# Jump_Stater.net
KiCad netlist of a schematic drawn in Altium Designer
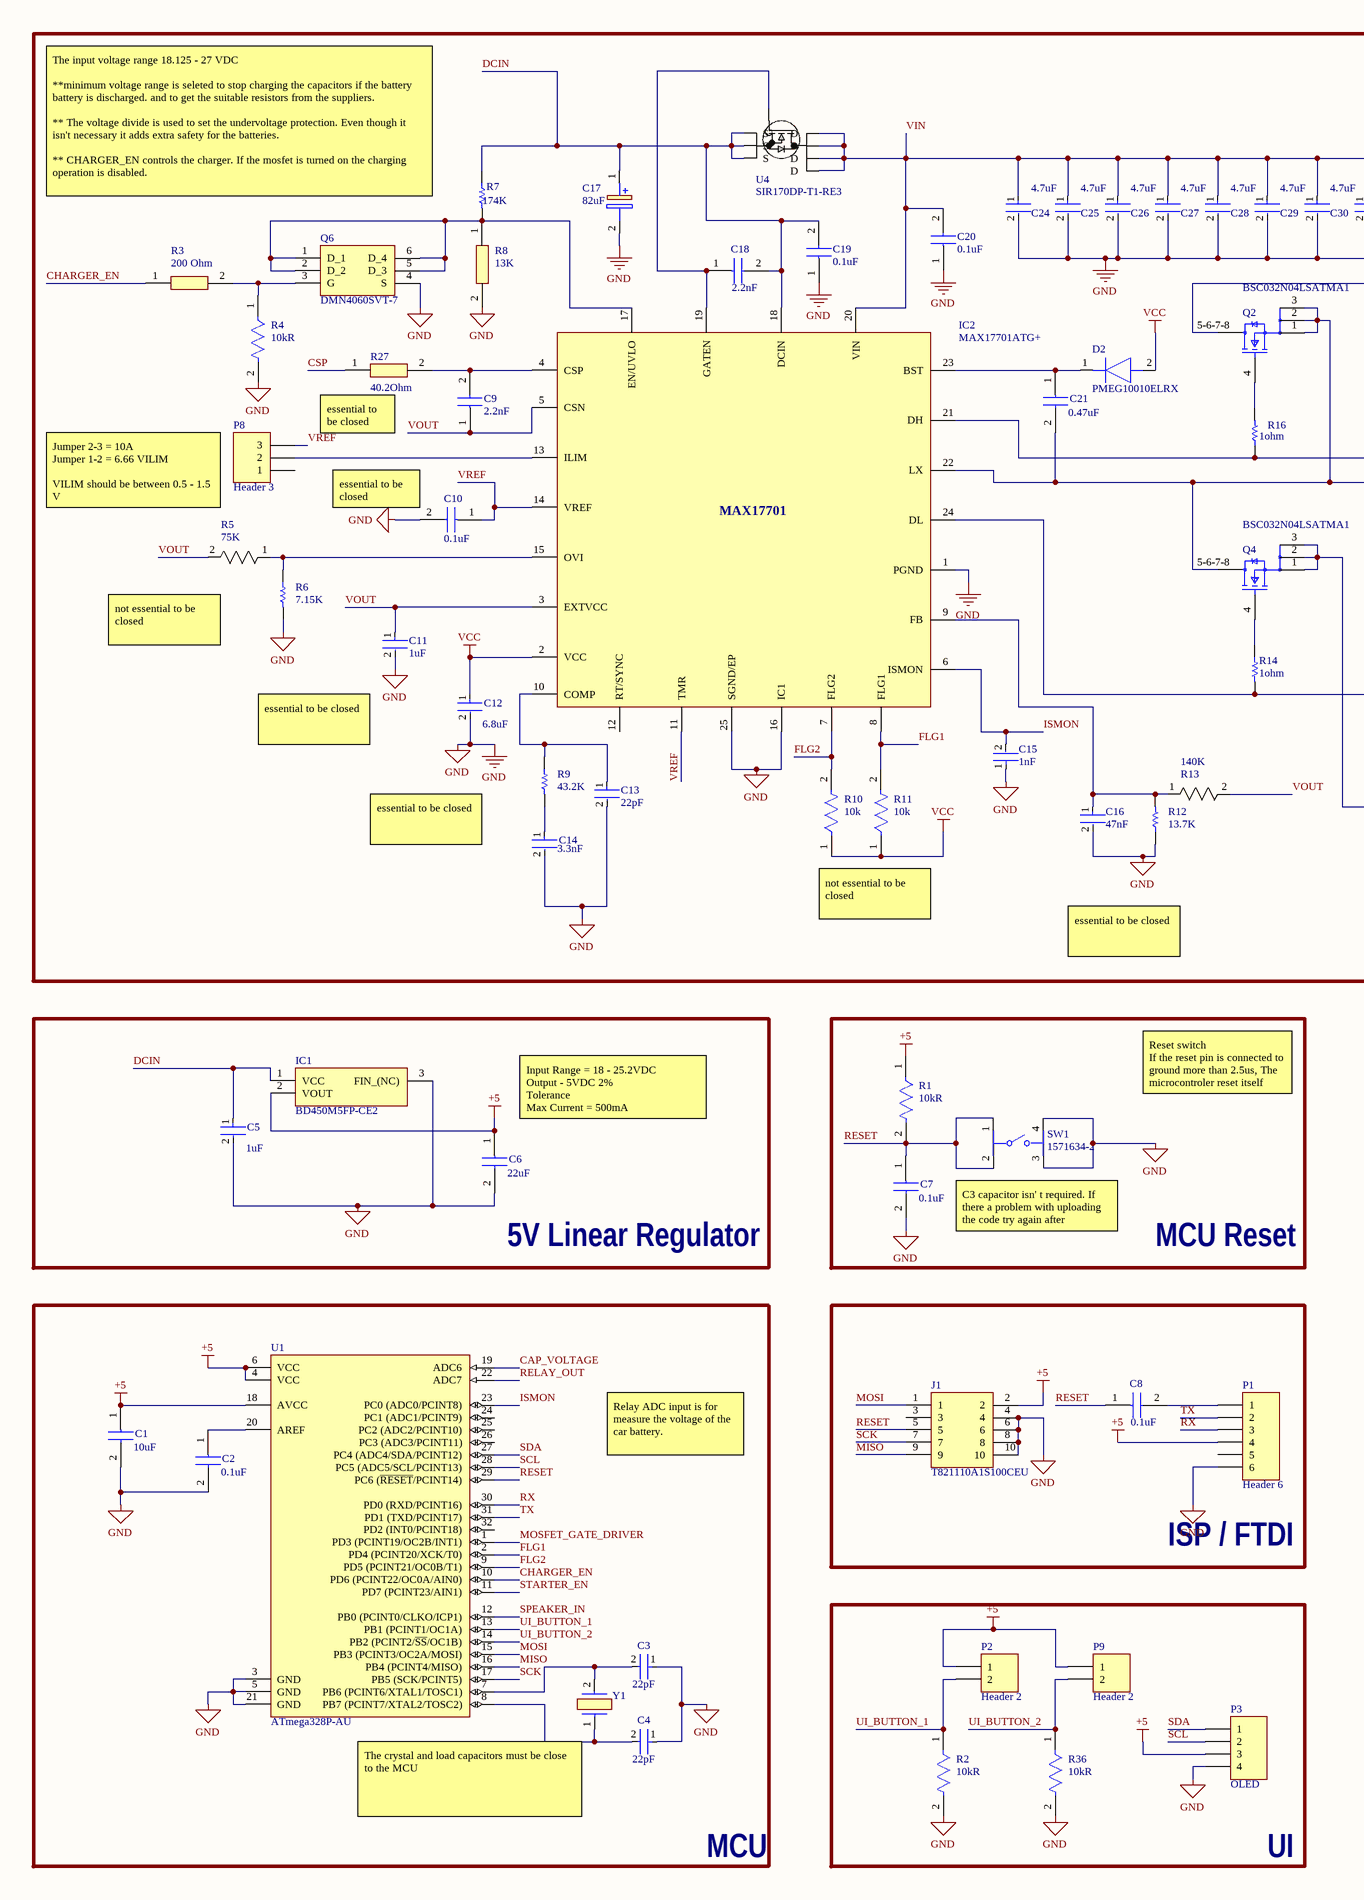
[diagram p0: Jump Stater.SchDoc, left]
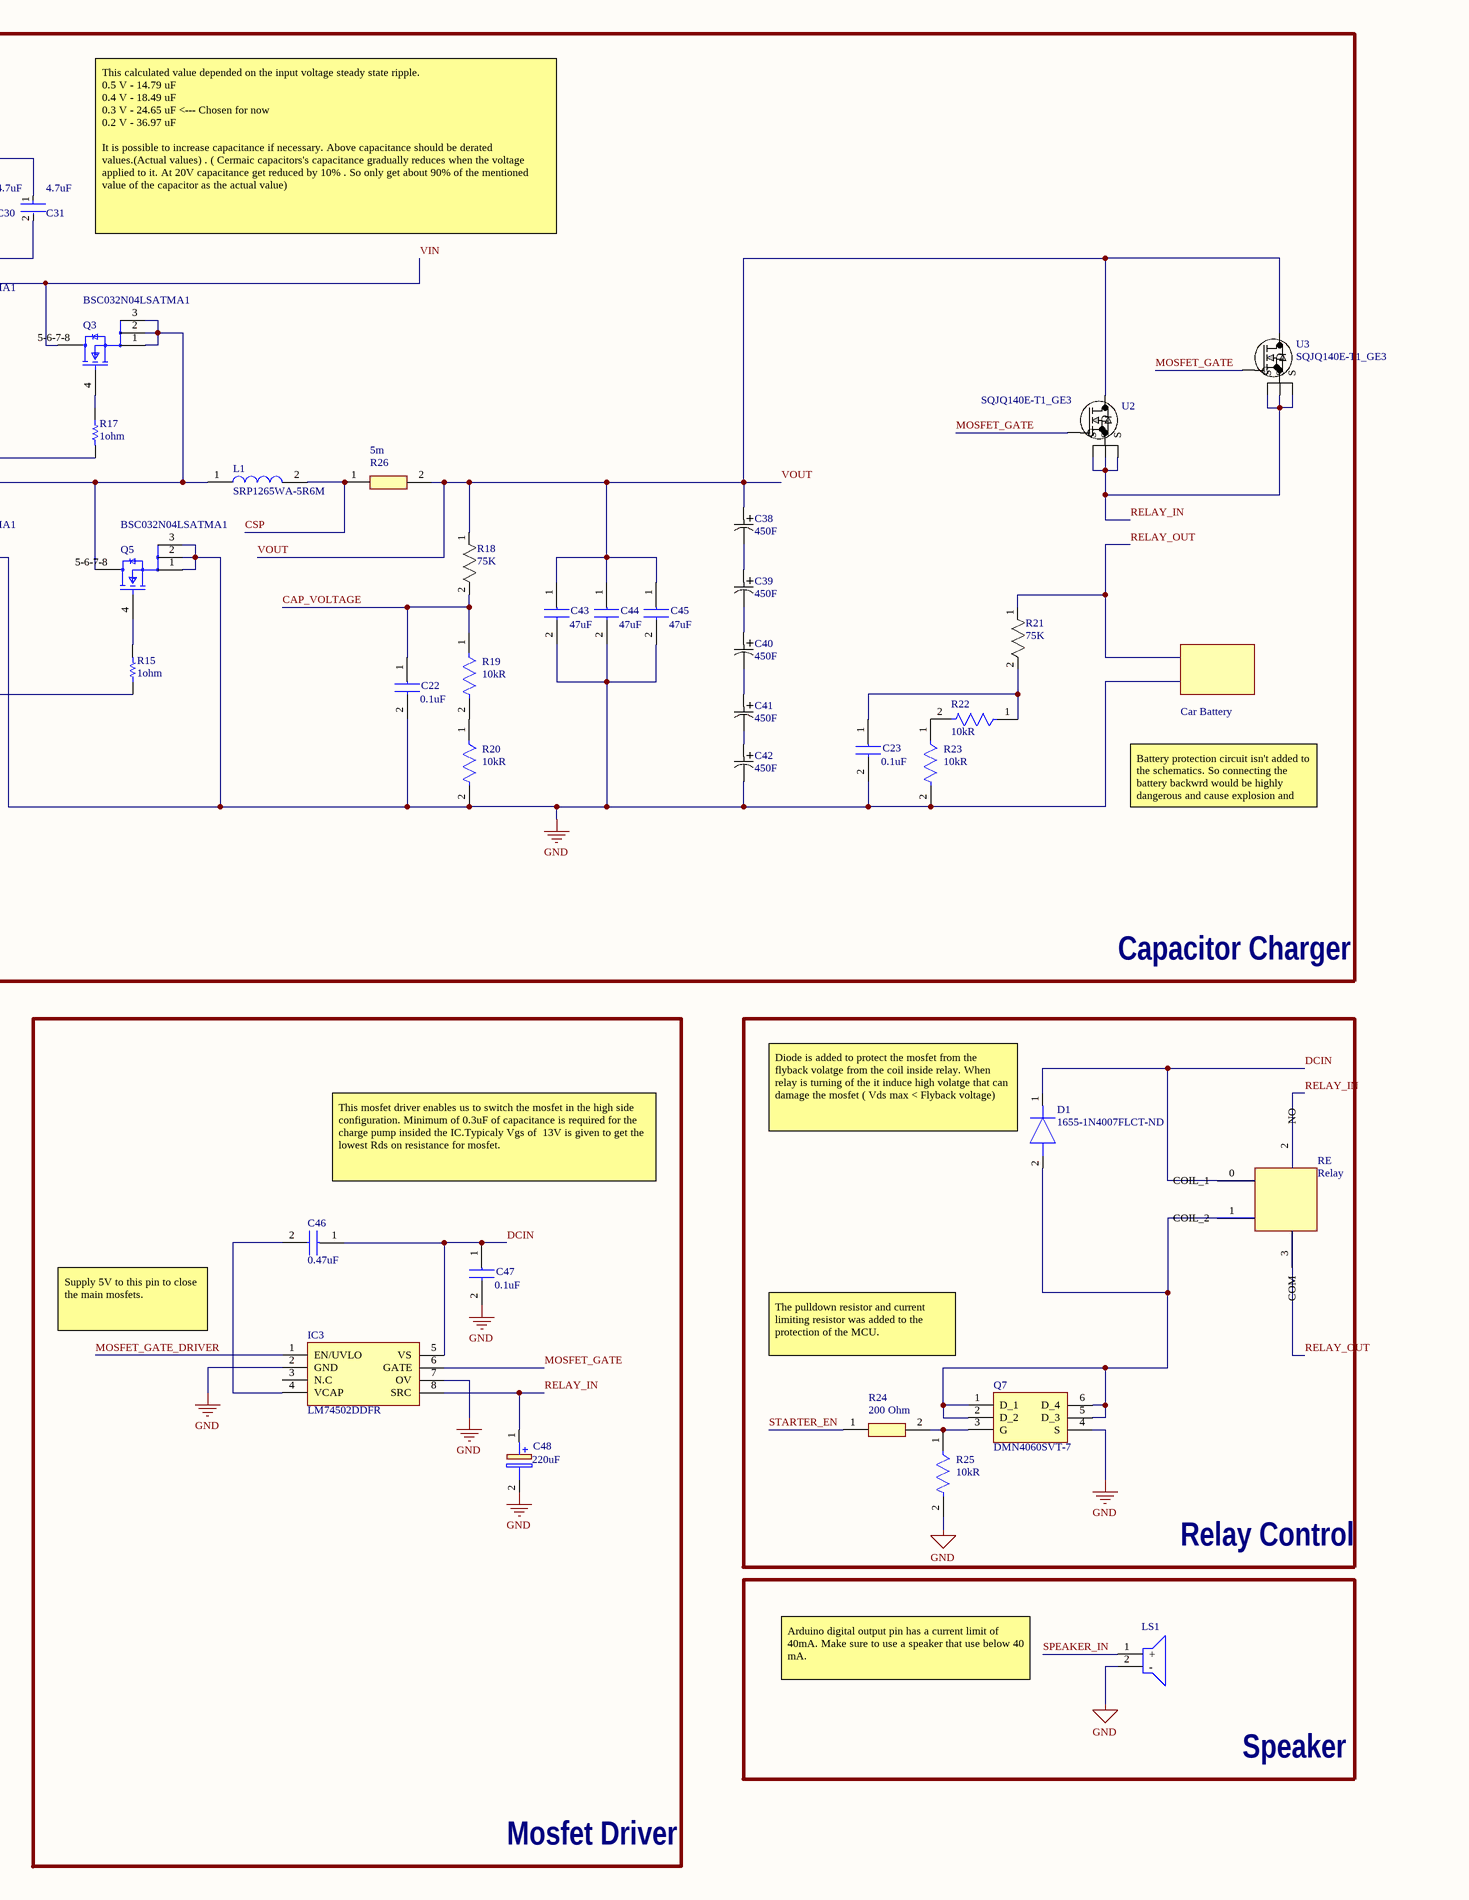
[diagram p1: Jump Stater.SchDoc, right]

(export (version "E")
  (design (tool "Eeschema 10.0.6"))
  (components
    (comp (ref "C1")
      (value "CL31A106MAHNNNE")
      (footprint "SamacSys:CAPC3216X180N")
      (description "CAP CER 10UF 25V X5R 1206 CL31A106MAHNNNE")
      (fields (field (name "MOUSER PART NUMBER") "187-CL31A106MAHNNNE") (field (name "CAPACITANCE") "10uF"))
      (libsource (lib "SamacSys") (part "CL31A106MAHNNNE"))
    )
    (comp (ref "C2")
      (value "CL31B104KBCNNNC")
      (footprint "SamacSys:CAPC3216X100N")
      (description "CAP CER 0.1UF 50V X7R 1206")
      (fields (field (name "MOUSER PART NUMBER") "187-CL31B104KBCNNNC") (field (name "CAPACITANCE") "0.1uF"))
      (libsource (lib "SamacSys") (part "CL31B104KBCNNNC"))
    )
    (comp (ref "C3")
      (value "CL31C220JBCNNNC")
      (footprint "FP-CL31-IPC_A")
      (description "Cap Ceramic 22pF 50V C0G ±5% SMD 1206 +125°C Embossed T/R")
      (fields
        (field (name "VOLTAGE") "50V")
        (field (name "TOLERANCE") "5%")
        (field (name "CAPACITANCE") "22pF")
      )
      (libsource (lib "Altium Content Vault") (part "b4654b650e69147ec39a6b967a45e02"))
    )
    (comp (ref "C4")
      (value "CL31C220JBCNNNC")
      (footprint "FP-CL31-IPC_A")
      (description "Cap Ceramic 22pF 50V C0G ±5% SMD 1206 +125°C Embossed T/R")
      (fields
        (field (name "VOLTAGE") "50V")
        (field (name "TOLERANCE") "5%")
        (field (name "CAPACITANCE") "22pF")
      )
      (libsource (lib "Altium Content Vault") (part "b4654b650e69147ec39a6b967a45e02"))
    )
    (comp (ref "C5")
      (value "CL31B105KBHNNNE")
      (footprint "FP-CL31-IPC_B")
      (description "Cap Ceramic 1uF 50V X7R ±10% SMD 1206 +125°C Embossed T/R")
      (fields
        (field (name "VOLTAGE") "50V")
        (field (name "CAPACITANCE") "1uF")
        (field (name "TOLERANCE") "10%")
      )
      (libsource (lib "Altium Content Vault") (part "b4654b650e69147ec39a6b967a45e02"))
    )
    (comp (ref "C6")
      (value "A766EB226M1DLAE060")
      (footprint "SamacSys:CAPAE660X600N")
      (description "CAP ALUM POLY 22UF 20% 20V SMD")
      (fields (field (name "MOUSER PART NUMBER") "80-A766EB226M1DLAE60") (field (name "CAPACITANCE") "22uF"))
      (libsource (lib "SamacSys") (part "A766EB226M1DLAE060"))
    )
    (comp (ref "C7")
      (value "CL31B104KBCNNNC")
      (footprint "SamacSys:CAPC3216X100N")
      (description "CAP CER 0.1UF 50V X7R 1206")
      (fields (field (name "MOUSER PART NUMBER") "187-CL31B104KBCNNNC") (field (name "CAPACITANCE") "0.1uF"))
      (libsource (lib "SamacSys") (part "CL31B104KBCNNNC"))
    )
    (comp (ref "C8")
      (value "CL31B104KBCNNNC")
      (footprint "SamacSys:CAPC3216X100N")
      (description "CAP CER 0.1UF 50V X7R 1206 CL31B104KBCNNNC")
      (fields (field (name "MOUSER PART NUMBER") "187-CL31B104KBCNNNC") (field (name "CAPACITANCE") "0.1uF"))
      (libsource (lib "SamacSys") (part "CL31B104KBCNNNC"))
    )
    (comp (ref "C9")
      (value "1206B222K500CT")
      (footprint "SamacSys:CAPC3216X90N")
      (description "Capacitor")
      (fields (field (name "CAPACITANCE") "2.2nF"))
      (libsource (lib "SamacSys") (part "1206B222K500CT"))
    )
    (comp (ref "C10")
      (value "CL31B104KBCNNNC")
      (footprint "SamacSys:CAPC3216X100N")
      (description "CAP CER 0.1UF 50V X7R 1206")
      (fields (field (name "MOUSER PART NUMBER") "187-CL31B104KBCNNNC") (field (name "CAPACITANCE") "0.1uF"))
      (libsource (lib "SamacSys") (part "CL31B104KBCNNNC"))
    )
    (comp (ref "C11")
      (value "CL31B105KBHNNNE")
      (footprint "FP-CL31-IPC_B")
      (description "Cap Ceramic 1uF 50V X7R ±10% SMD 1206 +125°C Embossed T/R")
      (fields
        (field (name "VOLTAGE") "50V")
        (field (name "CAPACITANCE") "1uF")
        (field (name "TOLERANCE") "10%")
      )
      (libsource (lib "Altium Content Vault") (part "b4654b650e69147ec39a6b967a45e02"))
    )
    (comp (ref "C12")
      (value "C3216X7R1C685K160AC")
      (footprint "FP-C3216-160-0_2-IPC_A")
      (description "Multilayer Ceramic Capacitors 6.8uF ±10% 16V X7R SMD 1206")
      (fields
        (field (name "CAPACITANCE") "6.8uF")
        (field (name "TOLERANCE") "10%")
        (field (name "VOLTAGE") "16V")
      )
      (libsource (lib "Altium Content Vault") (part "11868f565c42a9108669ba33697ecf6"))
    )
    (comp (ref "C13")
      (value "CL31C220JBCNNNC")
      (footprint "FP-CL31-IPC_A")
      (description "Cap Ceramic 22pF 50V C0G ±5% SMD 1206 +125°C Embossed T/R")
      (fields
        (field (name "VOLTAGE") "50V")
        (field (name "TOLERANCE") "5%")
        (field (name "CAPACITANCE") "22pF")
      )
      (libsource (lib "Altium Content Vault") (part "b4654b650e69147ec39a6b967a45e02"))
    )
    (comp (ref "C14")
      (value "12065A332JAT2A")
      (footprint "FP-1206-L_3_2_0_2-W_1_6_0-MFG")
      (description "General Purpose Ceramic Capacitor, 1206, 3.3nF, 5%, NP0, 30ppm/°C, 50V")
      (fields
        (field (name "CAPACITANCE") "3.3nF")
        (field (name "VOLTAGE") "50V")
        (field (name "TOLERANCE") "5%")
      )
      (libsource (lib "Altium Content Vault") (part "b4654b650e69147ec39a6b967a45e02"))
    )
    (comp (ref "C15")
      (value "CL31B102KBCNNNC")
      (footprint "FP-CL31-IPC_C")
      (description "Cap Ceramic 1nF 50V X7R ±10% SMD 1206 +125°C Embossed T/R")
      (fields
        (field (name "VOLTAGE") "63V")
        (field (name "TOLERANCE") "10%")
        (field (name "CAPACITANCE") "1nF")
      )
      (libsource (lib "Altium Content Vault") (part "b4654b650e69147ec39a6b967a45e02"))
    )
    (comp (ref "C16")
      (value "CL31B473KBCNNNC")
      (footprint "FP-CL31-IPC_B")
      (description "Cap Ceramic 47nF 50V X7R ±10% SMD 1206 +125°C Embossed T/R")
      (fields
        (field (name "TOLERANCE") "10%")
        (field (name "CAPACITANCE") "47nF")
        (field (name "VOLTAGE") "50V")
      )
      (libsource (lib "Altium Content Vault") (part "b4654b650e69147ec39a6b967a45e02"))
    )
    (comp (ref "C17")
      (value "A768KS826M1HLAS020")
      (footprint "CAPAE830X1240N")
      (description "CAP ALUM POLY 82UF 20% 50V SMD")
      (fields (field (name "MOUSER PART NUMBER") "80-A768KS826M1HLAS20") (field (name "CAPACITANCE") "82uF"))
      (libsource (lib "SamacSys") (part "A768KS826M1HLAS020"))
    )
    (comp (ref "C18")
      (value "1206B222K500CT")
      (footprint "SamacSys:CAPC3216X90N")
      (description "Capacitor")
      (fields (field (name "CAPACITANCE") "2.2nF"))
      (libsource (lib "SamacSys") (part "1206B222K500CT"))
    )
    (comp (ref "C19")
      (value "CL31B104KBCNNNC")
      (footprint "SamacSys:CAPC3216X100N")
      (description "CAP CER 0.1UF 50V X7R 1206")
      (fields (field (name "MOUSER PART NUMBER") "187-CL31B104KBCNNNC") (field (name "CAPACITANCE") "0.1uF"))
      (libsource (lib "SamacSys") (part "CL31B104KBCNNNC"))
    )
    (comp (ref "C20")
      (value "CL31B104KBCNNNC")
      (footprint "SamacSys:CAPC3216X100N")
      (description "CAP CER 0.1UF 50V X7R 1206")
      (fields (field (name "MOUSER PART NUMBER") "187-CL31B104KBCNNNC") (field (name "CAPACITANCE") "0.1uF"))
      (libsource (lib "SamacSys") (part "CL31B104KBCNNNC"))
    )
    (comp (ref "C21")
      (value "CL31B474KBHNNNE")
      (footprint "SamacSys:CAPC3216X180N")
      (description "CAP CER 0.47UF 50V X7R 1206")
      (fields (field (name "MOUSER PART NUMBER") "187-CL31B474KBHNNNE") (field (name "CAPACITANCE") "0.47uF"))
      (libsource (lib "*") (part "CL31B474KBHNNNE"))
    )
    (comp (ref "C22")
      (value "CL31B104KBCNNNC")
      (footprint "SamacSys:CAPC3216X100N")
      (description "CAP CER 0.1UF 50V X7R 1206")
      (fields (field (name "MOUSER PART NUMBER") "187-CL31B104KBCNNNC") (field (name "CAPACITANCE") "0.1uF"))
      (libsource (lib "SamacSys") (part "CL31B104KBCNNNC"))
    )
    (comp (ref "C23")
      (value "CL31B104KBCNNNC")
      (footprint "SamacSys:CAPC3216X100N")
      (description "CAP CER 0.1UF 50V X7R 1206")
      (fields (field (name "MOUSER PART NUMBER") "187-CL31B104KBCNNNC") (field (name "CAPACITANCE") "0.1uF"))
      (libsource (lib "SamacSys") (part "CL31B104KBCNNNC"))
    )
    (comp (ref "C24")
      (value "GRM319R61H475KA12D")
      (footprint "FP-GRM319-0_15-IPC_C")
      (description "Chip Multilayer Ceramic Capacitors for General Purpose, 1206, 4.7uF, X5R, 15%, 10%, 50V")
      (fields
        (field (name "VOLTAGE") "50V")
        (field (name "TOLERANCE") "10%")
        (field (name "CAPACITANCE") "4.7uF")
      )
      (libsource (lib "Altium Content Vault") (part "b4654b650e69147ec39a6b967a45e02"))
    )
    (comp (ref "C25")
      (value "GRM319R61H475KA12D")
      (footprint "FP-GRM319-0_15-IPC_C")
      (description "Chip Multilayer Ceramic Capacitors for General Purpose, 1206, 4.7uF, X5R, 15%, 10%, 50V")
      (fields
        (field (name "VOLTAGE") "50V")
        (field (name "TOLERANCE") "10%")
        (field (name "CAPACITANCE") "4.7uF")
      )
      (libsource (lib "Altium Content Vault") (part "b4654b650e69147ec39a6b967a45e02"))
    )
    (comp (ref "C26")
      (value "GRM319R61H475KA12D")
      (footprint "FP-GRM319-0_15-IPC_C")
      (description "Chip Multilayer Ceramic Capacitors for General Purpose, 1206, 4.7uF, X5R, 15%, 10%, 50V")
      (fields
        (field (name "VOLTAGE") "50V")
        (field (name "TOLERANCE") "10%")
        (field (name "CAPACITANCE") "4.7uF")
      )
      (libsource (lib "Altium Content Vault") (part "b4654b650e69147ec39a6b967a45e02"))
    )
    (comp (ref "C27")
      (value "GRM319R61H475KA12D")
      (footprint "FP-GRM319-0_15-IPC_C")
      (description "Chip Multilayer Ceramic Capacitors for General Purpose, 1206, 4.7uF, X5R, 15%, 10%, 50V")
      (fields
        (field (name "VOLTAGE") "50V")
        (field (name "TOLERANCE") "10%")
        (field (name "CAPACITANCE") "4.7uF")
      )
      (libsource (lib "Altium Content Vault") (part "b4654b650e69147ec39a6b967a45e02"))
    )
    (comp (ref "C28")
      (value "GRM319R61H475KA12D")
      (footprint "FP-GRM319-0_15-IPC_C")
      (description "Chip Multilayer Ceramic Capacitors for General Purpose, 1206, 4.7uF, X5R, 15%, 10%, 50V")
      (fields
        (field (name "VOLTAGE") "50V")
        (field (name "TOLERANCE") "10%")
        (field (name "CAPACITANCE") "4.7uF")
      )
      (libsource (lib "Altium Content Vault") (part "b4654b650e69147ec39a6b967a45e02"))
    )
    (comp (ref "C29")
      (value "GRM319R61H475KA12D")
      (footprint "FP-GRM319-0_15-IPC_C")
      (description "Chip Multilayer Ceramic Capacitors for General Purpose, 1206, 4.7uF, X5R, 15%, 10%, 50V")
      (fields
        (field (name "VOLTAGE") "50V")
        (field (name "TOLERANCE") "10%")
        (field (name "CAPACITANCE") "4.7uF")
      )
      (libsource (lib "Altium Content Vault") (part "b4654b650e69147ec39a6b967a45e02"))
    )
    (comp (ref "C30")
      (value "GRM319R61H475KA12D")
      (footprint "FP-GRM319-0_15-IPC_C")
      (description "Chip Multilayer Ceramic Capacitors for General Purpose, 1206, 4.7uF, X5R, 15%, 10%, 50V")
      (fields
        (field (name "VOLTAGE") "50V")
        (field (name "TOLERANCE") "10%")
        (field (name "CAPACITANCE") "4.7uF")
      )
      (libsource (lib "Altium Content Vault") (part "b4654b650e69147ec39a6b967a45e02"))
    )
    (comp (ref "C31")
      (value "GRM319R61H475KA12D")
      (footprint "FP-GRM319-0_15-IPC_C")
      (description "Chip Multilayer Ceramic Capacitors for General Purpose, 1206, 4.7uF, X5R, 15%, 10%, 50V")
      (fields
        (field (name "VOLTAGE") "50V")
        (field (name "TOLERANCE") "10%")
        (field (name "CAPACITANCE") "4.7uF")
      )
      (libsource (lib "Altium Content Vault") (part "b4654b650e69147ec39a6b967a45e02"))
    )
    (comp (ref "C38")
      (value "450F")
      (footprint "PCAP_TPLH-3R0/450SS35X71_TCT")
      (description "No Description Available")
      (libsource (lib "TPLH-3R0&slash_450SS35X71") (part "TPLH-3R0/450SS35X71"))
    )
    (comp (ref "C39")
      (value "450F")
      (footprint "PCAP_TPLH-3R0/450SS35X71_TCT")
      (description "No Description Available")
      (libsource (lib "TPLH-3R0&slash_450SS35X71") (part "TPLH-3R0/450SS35X71"))
    )
    (comp (ref "C40")
      (value "450F")
      (footprint "PCAP_TPLH-3R0/450SS35X71_TCT")
      (description "No Description Available")
      (libsource (lib "TPLH-3R0&slash_450SS35X71") (part "TPLH-3R0/450SS35X71"))
    )
    (comp (ref "C41")
      (value "450F")
      (footprint "PCAP_TPLH-3R0/450SS35X71_TCT")
      (description "No Description Available")
      (libsource (lib "TPLH-3R0&slash_450SS35X71") (part "TPLH-3R0/450SS35X71"))
    )
    (comp (ref "C42")
      (value "450F")
      (footprint "PCAP_TPLH-3R0/450SS35X71_TCT")
      (description "No Description Available")
      (libsource (lib "TPLH-3R0&slash_450SS35X71") (part "TPLH-3R0/450SS35X71"))
    )
    (comp (ref "C43")
      (value "C3216X5R1E476M160AC.")
      (footprint "SamacSys:CAPC3216X180N")
      (description "47 µF ±20% 25V Ceramic Capacitor X5R 1206 (3216 Metric)")
      (fields (field (name "CAPACITANCE") "47uF"))
      (libsource (lib "SamacSys") (part "C3216X5R1E476M160AC."))
    )
    (comp (ref "C44")
      (value "C3216X5R1E476M160AC.")
      (footprint "SamacSys:CAPC3216X180N")
      (description "47 µF ±20% 25V Ceramic Capacitor X5R 1206 (3216 Metric)")
      (fields (field (name "CAPACITANCE") "47uF"))
      (libsource (lib "SamacSys") (part "C3216X5R1E476M160AC."))
    )
    (comp (ref "C45")
      (value "C3216X5R1E476M160AC.")
      (footprint "SamacSys:CAPC3216X180N")
      (description "47 µF ±20% 25V Ceramic Capacitor X5R 1206 (3216 Metric)")
      (fields (field (name "CAPACITANCE") "47uF"))
      (libsource (lib "SamacSys") (part "C3216X5R1E476M160AC."))
    )
    (comp (ref "C46")
      (value "CL31B474KBHNNNE")
      (footprint "SamacSys:CAPC3216X180N")
      (description "CAP CER 0.47UF 50V X7R 1206")
      (fields (field (name "MOUSER PART NUMBER") "187-CL31B474KBHNNNE") (field (name "CAPACITANCE") "0.47uF"))
      (libsource (lib "SamacSys") (part "CL31B474KBHNNNE"))
    )
    (comp (ref "C47")
      (value "CL31B104KBCNNNC")
      (footprint "SamacSys:CAPC3216X100N")
      (description "CAP CER 0.1UF 50V X7R 1206")
      (fields (field (name "MOUSER PART NUMBER") "187-CL31B104KBCNNNC") (field (name "CAPACITANCE") "0.1uF"))
      (libsource (lib "SamacSys") (part "CL31B104KBCNNNC"))
    )
    (comp (ref "C48")
      (value "A768MS227M1GLAS022")
      (footprint "SamacSys:CAPAE1030X1270N")
      (description "Capacitor Polarised")
      (fields (field (name "CAPACITOR") "220uF"))
      (libsource (lib "SamacSys") (part "A768MS227M1GLAS022"))
    )
    (comp (ref "D1")
      (value "1655-1N4007FLCT-ND")
      (footprint "SODFL3718X140N")
      (description "Diode")
      (fields (field (name "MANUFACTURER_PART_NUMBER") "1N4007FLTR"))
      (libsource (lib "SamacSys") (part "1N4007FLTR"))
    )
    (comp (ref "D2")
      (value "PMEG10010ELRX")
      (footprint "SamacSys:SODFL3517X110N")
      (description "Diode")
      (fields (field (name "MOUSER PART NUMBER") "771-PMEG10010ELRX"))
      (libsource (lib "*") (part "PMEG10010ELRX"))
    )
    (comp (ref "IC1")
      (value "BD450M5FP-CE2")
      (footprint "SamacSys:ROHM_TO-252-3")
      (description "Integrated Circuit")
      (fields (field (name "MOUSER PART NUMBER") "755-BD450M5FP-CE2"))
      (libsource (lib "SamacSys") (part "BD450M5FP-CE2"))
    )
    (comp (ref "IC2")
      (value "MAX17701ATG+")
      (footprint "SamacSys:QFN50P400X400X80-25N-D")
      (description "Integrated Circuit")
      (fields (field (name "MOUSER PART NUMBER") "700-MAX17701ATG+"))
      (libsource (lib "SamacSys") (part "MAX17701ATG+"))
    )
    (comp (ref "IC3")
      (value "LM74502DDFR")
      (footprint "SamacSys:SOT65P280X110-8N")
      (description "Integrated Circuit")
      (fields (field (name "MOUSER PART NUMBER") "595-LM74502DDFR"))
      (libsource (lib "*") (part "LM74502DDFR"))
    )
    (comp (ref "J1")
      (value "T821110A1S100CEU")
      (footprint "SamacSys:SHDR10W64P254X254_2X5_2032X895X915P")
      (description "Connector")
      (libsource (lib "SamacSys") (part "T821110A1S100CEU"))
    )
    (comp (ref "L1")
      (value "SRP1265WA-5R6M")
      (footprint "SamacSys:SRP1265WA5R6M")
      (description "Inductor")
      (fields (field (name "MOUSER PART NUMBER") "652-SRP1265WA-5R6M"))
      (libsource (lib "SamacSys") (part "SRP1265WA-5R6M"))
    )
    (comp (ref "LS1")
      (value "~")
      (footprint "CMI12950585T")
      (description "Loudspeaker or Buzzer")
      (fields
        (field (name "MANUFACTURER_PART_NUMBER") "CMI-1295-0585T")
        (field (name "MOUSER PART NUMBER") "490-CMI-1295-0585T")
      )
      (libsource (lib "SamacSys") (part "CMI-1295-0585T"))
    )
    (comp (ref "P1")
      (value "Header 6")
      (footprint "HDR1X6")
      (description "Header, 6-Pin")
      (fields (field (name "PUBLISHER") "Altium Limited"))
      (libsource (lib "Miscellaneous Connectors") (part "Header 6"))
    )
    (comp (ref "P2")
      (value "Header 2")
      (footprint "HDR1X2")
      (description "Header, 2-Pin")
      (fields (field (name "PUBLISHER") "Altium Limited"))
      (libsource (lib "Miscellaneous Connectors") (part "Header 2"))
    )
    (comp (ref "P3")
      (value "OLED")
      (footprint "HDR1X4")
      (description "Header, 4-Pin")
      (fields (field (name "PUBLISHER") "Altium Limited"))
      (libsource (lib "Miscellaneous Connectors") (part "Header 4"))
    )
    (comp (ref "P8")
      (value "Header 3")
      (footprint "HDR1X3")
      (description "Header, 3-Pin")
      (fields (field (name "PUBLISHER") "Altium Limited"))
      (libsource (lib "Miscellaneous Connectors") (part "Header 3"))
    )
    (comp (ref "P9")
      (value "Header 2")
      (footprint "HDR1X2")
      (description "Header, 2-Pin")
      (fields (field (name "PUBLISHER") "Altium Limited"))
      (libsource (lib "Miscellaneous Connectors") (part "Header 2"))
    )
    (comp (ref "Q2")
      (value "BSC032N04LSATMA1")
      (footprint "FP-PG-TDSON-8-MFG")
      (description "MOSFET N-CH 40V 21A/98A TDSON")
      (libsource (lib "Altium Content Vault") (part "3daf4540832f5b2d6d8f0ce0a097f6c"))
    )
    (comp (ref "Q3")
      (value "BSC032N04LSATMA1")
      (footprint "FP-PG-TDSON-8-MFG")
      (description "MOSFET N-CH 40V 21A/98A TDSON")
      (libsource (lib "Altium Content Vault") (part "3daf4540832f5b2d6d8f0ce0a097f6c"))
    )
    (comp (ref "Q4")
      (value "BSC032N04LSATMA1")
      (footprint "FP-PG-TDSON-8-MFG")
      (description "MOSFET N-CH 40V 21A/98A TDSON")
      (libsource (lib "Altium Content Vault") (part "3daf4540832f5b2d6d8f0ce0a097f6c"))
    )
    (comp (ref "Q5")
      (value "BSC032N04LSATMA1")
      (footprint "FP-PG-TDSON-8-MFG")
      (description "MOSFET N-CH 40V 21A/98A TDSON")
      (libsource (lib "Altium Content Vault") (part "3daf4540832f5b2d6d8f0ce0a097f6c"))
    )
    (comp (ref "Q6")
      (value "DMN4060SVT-7")
      (footprint "SamacSys:SOT95P280X100-6N")
      (description "MOSFET (N-Channel)")
      (fields (field (name "MOUSER PART NUMBER") "621-DMN4060SVT-7"))
      (libsource (lib "*") (part "DMN4060SVT-7"))
    )
    (comp (ref "Q7")
      (value "DMN4060SVT-7")
      (footprint "SamacSys:SOT95P280X100-6N")
      (description "MOSFET (N-Channel)")
      (fields (field (name "MOUSER PART NUMBER") "621-DMN4060SVT-7"))
      (libsource (lib "*") (part "DMN4060SVT-7"))
    )
    (comp (ref "R1")
      (value "RMCF1206FT10K0")
      (footprint "FP-RMCF1206-IPC_B")
      (description "10kΩ ±1% 0.25W 1206 Thick Film Chip Resistor AEC-Q200 compliant RMCF1206FT10K0")
      (fields (field (name "RESISTANCE") "10kR") (field (name "TOLERANCE") "1%"))
      (libsource (lib "Altium Content Vault") (part "1029c3af85768c4190bb7ad29bc67b5"))
    )
    (comp (ref "R2")
      (value "RMCF1206FT10K0")
      (footprint "FP-RMCF1206-IPC_B")
      (description "10kΩ ±1% 0.25W 1206 Thick Film Chip Resistor AEC-Q200 compliant")
      (fields (field (name "RESISTANCE") "10kR") (field (name "TOLERANCE") "1%"))
      (libsource (lib "Altium Content Vault") (part "1029c3af85768c4190bb7ad29bc67b5"))
    )
    (comp (ref "R3")
      (value "RMCF1206FT200R")
      (footprint "RESC3216X70N")
      (description "RES 200 OHM 1% 1/4W 1206")
      (fields (field (name "RESISTANCE") "200 Ohm"))
      (libsource (lib "SamacSys") (part "RMCF1206FT200R"))
    )
    (comp (ref "R4")
      (value "RMCF1206FT10K0")
      (footprint "FP-RMCF1206-IPC_B")
      (description "10kΩ ±1% 0.25W 1206 Thick Film Chip Resistor AEC-Q200 compliant RMCF1206FT10K0")
      (fields (field (name "RESISTANCE") "10kR") (field (name "TOLERANCE") "1%"))
      (libsource (lib "Altium Content Vault") (part "1029c3af85768c4190bb7ad29bc67b5"))
    )
    (comp (ref "R5")
      (value "RC1206FR-0775KL")
      (footprint "RC1206N_YAG")
      (description "No Description Available")
      (fields (field (name "RESISTANCE") "75K"))
      (libsource (lib "RC1206FR-0775KL") (part "RC1206FR-0775KL"))
    )
    (comp (ref "R6")
      (value "RC1206FR-077K15L")
      (footprint "RESC3116X65X40ML10T20")
      (fields (field (name "MANUFACTURER") "Yageo") (field (name "RESISTANCE") "7.15K"))
      (libsource (lib "Altium Content Vault") (part "RES"))
    )
    (comp (ref "R7")
      (value "174K")
      (footprint "RESC1206(3216)_L")
      (description "174K 0.25W 1% 1206 (3216 Metric)  SMD")
      (fields (field (name "POWER") "0.25 W") (field (name "TOLERANCE") "1 %"))
      (libsource (lib "Altium Content Vault") (part "RES"))
    )
    (comp (ref "R8")
      (value "RC1206FR-0713KL")
      (footprint "SamacSys:RESC3116X65N")
      (description "Resistor")
      (fields (field (name "MOUSER PART NUMBER") "603-RC1206FR-0713KL") (field (name "RESISTANCE") "13K"))
      (libsource (lib "*") (part "RC1206FR-0713KL"))
    )
    (comp (ref "R9")
      (value "RC1206FR-0743K2L")
      (footprint "RESC3116X65X40ML10T20")
      (fields (field (name "MANUFACTURER") "Yageo") (field (name "RESISTANCE") "43.2K"))
      (libsource (lib "Altium Content Vault") (part "RES"))
    )
    (comp (ref "R10")
      (value "RMCF1206FT10K0")
      (footprint "FP-RMCF1206-IPC_B")
      (description "10kΩ ±1% 0.25W 1206 Thick Film Chip Resistor AEC-Q200 compliant RMCF1206FT10K0")
      (fields (field (name "RESISTANCE") "10k") (field (name "TOLERANCE") "1%"))
      (libsource (lib "Altium Content Vault") (part "1029c3af85768c4190bb7ad29bc67b5"))
    )
    (comp (ref "R11")
      (value "RMCF1206FT10K0")
      (footprint "FP-RMCF1206-IPC_B")
      (description "10kΩ ±1% 0.25W 1206 Thick Film Chip Resistor AEC-Q200 compliant RMCF1206FT10K0")
      (fields (field (name "RESISTANCE") "10k") (field (name "TOLERANCE") "1%"))
      (libsource (lib "Altium Content Vault") (part "1029c3af85768c4190bb7ad29bc67b5"))
    )
    (comp (ref "R12")
      (value "RK73H2BTTD1372F")
      (footprint "RESC3216X70X40ML20T20")
      (description "RES 13.7K OHM 1% 1/4W 1206")
      (fields (field (name "MANUFACTURER") "KOA Speer") (field (name "RESISTANCE") "13.7K"))
      (libsource (lib "Altium Content Vault") (part "RES"))
    )
    (comp (ref "R13")
      (value "RMCF1206FT140K")
      (footprint "RES_RMCF1206_STP")
      (description "No Description Available")
      (fields (field (name "RESISTANCE") "140K"))
      (libsource (lib "RMCF1206FT140K") (part "RMCF1206FT140K"))
    )
    (comp (ref "R14")
      (value "RK73H2BTTD1R00F")
      (footprint "RESC3216X70X40LL20T20")
      (fields (field (name "MANUFACTURER") "KOA Speer") (field (name "RESISTANCE") "1ohm"))
      (libsource (lib "Altium Content Vault") (part "RES"))
    )
    (comp (ref "R15")
      (value "RK73H2BTTD1R00F")
      (footprint "RESC3216X70X40LL20T20")
      (fields (field (name "MANUFACTURER") "KOA Speer") (field (name "RESISTANCE") "1ohm"))
      (libsource (lib "Altium Content Vault") (part "RES"))
    )
    (comp (ref "R16")
      (value "RK73H2BTTD1R00F")
      (footprint "RESC3216X70X40LL20T20")
      (fields (field (name "MANUFACTURER") "KOA Speer") (field (name "RESISTANCE") "1ohm"))
      (libsource (lib "Altium Content Vault") (part "RES"))
    )
    (comp (ref "R17")
      (value "RK73H2BTTD1R00F")
      (footprint "RESC3216X70X40LL20T20")
      (fields (field (name "MANUFACTURER") "KOA Speer") (field (name "RESISTANCE") "1ohm"))
      (libsource (lib "Altium Content Vault") (part "RES"))
    )
    (comp (ref "R18")
      (value "RC1206FR-0775KL")
      (footprint "RC1206N_YAG")
      (description "No Description Available")
      (fields (field (name "RESISTANCE") "75K"))
      (libsource (lib "RC1206FR-0775KL") (part "RC1206FR-0775KL"))
    )
    (comp (ref "R19")
      (value "RMCF1206FT10K0")
      (footprint "FP-RMCF1206-IPC_B")
      (description "10kΩ ±1% 0.25W 1206 Thick Film Chip Resistor AEC-Q200 compliant RMCF1206FT10K0")
      (fields (field (name "RESISTANCE") "10kR") (field (name "TOLERANCE") "1%"))
      (libsource (lib "Altium Content Vault") (part "1029c3af85768c4190bb7ad29bc67b5"))
    )
    (comp (ref "R20")
      (value "RMCF1206FT10K0")
      (footprint "FP-RMCF1206-IPC_B")
      (description "10kΩ ±1% 0.25W 1206 Thick Film Chip Resistor AEC-Q200 compliant RMCF1206FT10K0")
      (fields (field (name "RESISTANCE") "10kR") (field (name "TOLERANCE") "1%"))
      (libsource (lib "Altium Content Vault") (part "1029c3af85768c4190bb7ad29bc67b5"))
    )
    (comp (ref "R21")
      (value "RC1206FR-0775KL")
      (footprint "RC1206N_YAG")
      (description "No Description Available")
      (fields (field (name "RESISTANCE") "75K"))
      (libsource (lib "RC1206FR-0775KL") (part "RC1206FR-0775KL"))
    )
    (comp (ref "R22")
      (value "RMCF1206FT10K0")
      (footprint "FP-RMCF1206-IPC_B")
      (description "10kΩ ±1% 0.25W 1206 Thick Film Chip Resistor AEC-Q200 compliant RMCF1206FT10K0")
      (fields (field (name "RESISTANCE") "10kR") (field (name "TOLERANCE") "1%"))
      (libsource (lib "Altium Content Vault") (part "1029c3af85768c4190bb7ad29bc67b5"))
    )
    (comp (ref "R23")
      (value "RMCF1206FT10K0")
      (footprint "FP-RMCF1206-IPC_B")
      (description "10kΩ ±1% 0.25W 1206 Thick Film Chip Resistor AEC-Q200 compliant RMCF1206FT10K0")
      (fields (field (name "RESISTANCE") "10kR") (field (name "TOLERANCE") "1%"))
      (libsource (lib "Altium Content Vault") (part "1029c3af85768c4190bb7ad29bc67b5"))
    )
    (comp (ref "R24")
      (value "RMCF1206FT200R")
      (footprint "RESC3216X70N")
      (description "RES 200 OHM 1% 1/4W 1206")
      (fields (field (name "RESISTANCE") "200 Ohm"))
      (libsource (lib "SamacSys") (part "RMCF1206FT200R"))
    )
    (comp (ref "R25")
      (value "RMCF1206FT10K0")
      (footprint "FP-RMCF1206-IPC_B")
      (description "10kΩ ±1% 0.25W 1206 Thick Film Chip Resistor AEC-Q200 compliant RMCF1206FT10K0")
      (fields (field (name "RESISTANCE") "10kR") (field (name "TOLERANCE") "1%"))
      (libsource (lib "Altium Content Vault") (part "1029c3af85768c4190bb7ad29bc67b5"))
    )
    (comp (ref "R26")
      (value "CRF2512-FZ-R005ELF")
      (footprint "SamacSys:RESC6432X80N")
      (description "RES 0.005 OHM 1% 2W 2512")
      (fields (field (name "MOUSER PART NUMBER") "652-CRF2512FZR005ELF") (field (name "RESISTANCE") "5m"))
      (libsource (lib "SamacSys") (part "CRF2512-FZ-R005ELF"))
    )
    (comp (ref "R27")
      (value "CRT1206-BY-40R2ELF")
      (footprint "SamacSys:RESC3016X65N")
      (description "RES SMD 40.2 OHM 0.1% 1/4W 1206")
      (fields
        (field (name "MOUSER PART NUMBER") "652-CRT1206BY40R2ELF")
        (field (name "RESISTANCE") "40.2Ohm")
      )
      (libsource (lib "SamacSys") (part "CRT1206-BY-40R2ELF"))
    )
    (comp (ref "R36")
      (value "RMCF1206FT10K0")
      (footprint "FP-RMCF1206-IPC_B")
      (description "10kΩ ±1% 0.25W 1206 Thick Film Chip Resistor AEC-Q200 compliant")
      (fields (field (name "RESISTANCE") "10kR") (field (name "TOLERANCE") "1%"))
      (libsource (lib "Altium Content Vault") (part "1029c3af85768c4190bb7ad29bc67b5"))
    )
    (comp (ref "RE") (value "Relay") (footprint "PCBComponent_1") (libsource (lib "Relay") (part "Relay")))
    (comp (ref "SW1")
      (value "1571634-2")
      (footprint "FP-1571634-2-MFG")
      (description "SWITCH TACTILE SPST-NO 0.05A 24V")
      (libsource (lib "Altium Content Vault") (part "512b1658425e80dc09bd29e095ee4d3"))
    )
    (comp (ref "U1")
      (value "ATmega328P-AU")
      (footprint "32A_M")
      (libsource (lib "Altium Content Vault") (part "MC-8B-ATM48-SQ32"))
    )
    (comp (ref "U2")
      (value "SQJQ140E-T1_GE3")
      (footprint "DPAK_140E-T1_GE3_VIS")
      (description "No Description Available")
      (libsource (lib "SQJQ140E-T1_GE3") (part "SQJQ140E-T1_GE3"))
    )
    (comp (ref "U3")
      (value "SQJQ140E-T1_GE3")
      (footprint "DPAK_140E-T1_GE3_VIS")
      (description "No Description Available")
      (libsource (lib "SQJQ140E-T1_GE3") (part "SQJQ140E-T1_GE3"))
    )
    (comp (ref "U4")
      (value "SIR170DP-T1-RE3")
      (footprint "MOSFET_DP-T1-RE3_VIS")
      (description "No Description Available")
      (libsource (lib "SIR170DP-T1-RE3") (part "SIR170DP-T1-RE3"))
    )
    (comp (ref "Y1")
      (value "ECS-160-20-3X-TR")
      (footprint "SamacSys:ECS160203XTR")
      (description "Crystal or Oscillator")
      (fields (field (name "MOUSER PART NUMBER") "520-160-20-3XT"))
      (libsource (lib "SamacSys") (part "ECS-160-20-3X-TR"))
    )
  )
  (nets
    (net (code "1") (name "+5") (class "Default")
      (node (ref "C1") (pin "1") (pinfunction "1_1") (pintype "passive"))
      (node (ref "C6") (pin "1") (pinfunction "+_1") (pintype "passive"))
      (node (ref "IC1") (pin "2") (pinfunction "VOUT_2") (pintype "passive"))
      (node (ref "J1") (pin "2") (pinfunction "2_2") (pintype "passive"))
      (node (ref "P1") (pin "4") (pinfunction "4_4") (pintype "passive"))
      (node (ref "P2") (pin "1") (pinfunction "1_1") (pintype "passive"))
      (node (ref "P3") (pin "3") (pinfunction "3_3") (pintype "passive"))
      (node (ref "P9") (pin "1") (pinfunction "1_1") (pintype "passive"))
      (node (ref "R1") (pin "1") (pinfunction "1_1") (pintype "passive"))
      (node (ref "U1") (pin "18") (pinfunction "AVCC_18") (pintype "power_in"))
      (node (ref "U1") (pin "4") (pinfunction "VCC_4") (pintype "power_in"))
      (node (ref "U1") (pin "6") (pinfunction "VCC_6") (pintype "power_in"))
    )
    (net (code "2") (name "/CAP_VOLTAGE") (class "Default")
      (node (ref "C22") (pin "1") (pinfunction "1_1") (pintype "passive"))
      (node (ref "R18") (pin "2") (pinfunction "2_2") (pintype "passive"))
      (node (ref "R19") (pin "1") (pinfunction "1_1") (pintype "passive"))
      (node (ref "U1") (pin "19") (pinfunction "ADC6_19") (pintype "input"))
    )
    (net (code "3") (name "/CHARGER_EN") (class "Default")
      (node (ref "R3") (pin "1") (pinfunction "1_1") (pintype "passive"))
      (node (ref "U1") (pin "10") (pinfunction "PD6_(PCINT22/OC0A/AIN0)_10") (pintype "bidirectional"))
    )
    (net (code "4") (name "/CSP") (class "Default")
      (node (ref "L1") (pin "2") (pinfunction "2_2") (pintype "passive"))
      (node (ref "R26") (pin "1") (pinfunction "1_1") (pintype "passive"))
      (node (ref "R27") (pin "1") (pinfunction "1_1") (pintype "passive"))
    )
    (net (code "5") (name "/DCIN") (class "Default")
      (node (ref "C17") (pin "1") (pinfunction "+_1") (pintype "passive"))
      (node (ref "C18") (pin "2") (pinfunction "2_2") (pintype "passive"))
      (node (ref "C19") (pin "2") (pinfunction "2_2") (pintype "passive"))
      (node (ref "C46") (pin "1") (pinfunction "1_1") (pintype "passive"))
      (node (ref "C47") (pin "1") (pinfunction "1_1") (pintype "passive"))
      (node (ref "C5") (pin "1") (pinfunction "1_1") (pintype "passive"))
      (node (ref "D1") (pin "1") (pinfunction "K_1") (pintype "passive"))
      (node (ref "IC1") (pin "1") (pinfunction "VCC_1") (pintype "passive"))
      (node (ref "IC2") (pin "18") (pinfunction "DCIN_18") (pintype "passive"))
      (node (ref "IC3") (pin "5") (pinfunction "VS_5") (pintype "passive"))
      (node (ref "R7") (pin "1") (pinfunction "1_1") (pintype "passive"))
      (node (ref "RE") (pin "0") (pinfunction "COIL_1_0") (pintype "passive"))
      (node (ref "U4") (pin "1") (pinfunction "S_1") (pintype "passive"))
      (node (ref "U4") (pin "2") (pinfunction "S_2") (pintype "passive"))
      (node (ref "U4") (pin "3") (pinfunction "S_3") (pintype "passive"))
    )
    (net (code "6") (name "/FLG1") (class "Default")
      (node (ref "IC2") (pin "8") (pinfunction "FLG1_8") (pintype "passive"))
      (node (ref "R11") (pin "2") (pinfunction "2_2") (pintype "passive"))
      (node (ref "U1") (pin "2") (pinfunction "PD4_(PCINT20/XCK/T0)_2") (pintype "bidirectional"))
    )
    (net (code "7") (name "/FLG2") (class "Default")
      (node (ref "IC2") (pin "7") (pinfunction "FLG2_7") (pintype "passive"))
      (node (ref "R10") (pin "2") (pinfunction "2_2") (pintype "passive"))
      (node (ref "U1") (pin "9") (pinfunction "PD5_(PCINT21/OC0B/T1)_9") (pintype "bidirectional"))
    )
    (net (code "8") (name "/ISMON") (class "Default")
      (node (ref "C15") (pin "2") (pinfunction "2_2") (pintype "passive"))
      (node (ref "IC2") (pin "6") (pinfunction "ISMON_6") (pintype "passive"))
      (node (ref "U1") (pin "23") (pinfunction "PC0_(ADC0/PCINT8)_23") (pintype "bidirectional"))
    )
    (net (code "9") (name "/MISO") (class "Default")
      (node (ref "J1") (pin "9") (pinfunction "9_9") (pintype "passive"))
      (node (ref "U1") (pin "16") (pinfunction "PB4_(PCINT4/MISO)_16") (pintype "bidirectional"))
    )
    (net (code "10") (name "/MOSFET_GATE") (class "Default")
      (node (ref "IC3") (pin "6") (pinfunction "GATE_6") (pintype "passive"))
      (node (ref "U2") (pin "4") (pinfunction "G_4") (pintype "passive"))
      (node (ref "U3") (pin "4") (pinfunction "G_4") (pintype "passive"))
    )
    (net (code "11") (name "/MOSFET_GATE_DRIVER") (class "Default")
      (node (ref "IC3") (pin "1") (pinfunction "EN/UVLO_1") (pintype "passive"))
      (node (ref "U1") (pin "1") (pinfunction "PD3_(PCINT19/OC2B/INT1)_1") (pintype "bidirectional"))
    )
    (net (code "12") (name "/MOSI") (class "Default")
      (node (ref "J1") (pin "1") (pinfunction "1_1") (pintype "passive"))
      (node (ref "U1") (pin "15") (pinfunction "PB3_(PCINT3/OC2A/MOSI)_15") (pintype "bidirectional"))
    )
    (net (code "13") (name "/RELAY_IN") (class "Default")
      (node (ref "C48") (pin "1") (pinfunction "+_1") (pintype "passive"))
      (node (ref "IC3") (pin "8") (pinfunction "SRC_8") (pintype "passive"))
      (node (ref "RE") (pin "2") (pinfunction "NO_2") (pintype "passive"))
      (node (ref "U2") (pin "1") (pinfunction "S_1") (pintype "passive"))
      (node (ref "U2") (pin "2") (pinfunction "S_2") (pintype "passive"))
      (node (ref "U2") (pin "3") (pinfunction "S_3") (pintype "passive"))
      (node (ref "U3") (pin "1") (pinfunction "S_1") (pintype "passive"))
      (node (ref "U3") (pin "2") (pinfunction "S_2") (pintype "passive"))
      (node (ref "U3") (pin "3") (pinfunction "S_3") (pintype "passive"))
    )
    (net (code "14") (name "/RELAY_OUT") (class "Default")
      (node (ref "R21") (pin "1") (pinfunction "1_1") (pintype "passive"))
      (node (ref "RE") (pin "3") (pinfunction "COM_3") (pintype "passive"))
      (node (ref "U1") (pin "22") (pinfunction "ADC7_22") (pintype "input"))
    )
    (net (code "15") (name "/RESET") (class "Default")
      (node (ref "C7") (pin "1") (pinfunction "1_1") (pintype "passive"))
      (node (ref "C8") (pin "1") (pinfunction "1_1") (pintype "passive"))
      (node (ref "J1") (pin "5") (pinfunction "5_5") (pintype "passive"))
      (node (ref "R1") (pin "2") (pinfunction "2_2") (pintype "passive"))
      (node (ref "SW1") (pin "1") (pinfunction "1_1") (pintype "passive"))
      (node (ref "SW1") (pin "2") (pinfunction "2_2") (pintype "passive"))
      (node (ref "U1") (pin "29") (pinfunction "PC6_(~{RESET}/PCINT14)_29") (pintype "bidirectional"))
    )
    (net (code "16") (name "/RX") (class "Default")
      (node (ref "P1") (pin "3") (pinfunction "3_3") (pintype "passive"))
      (node (ref "U1") (pin "30") (pinfunction "PD0_(RXD/PCINT16)_30") (pintype "bidirectional"))
    )
    (net (code "17") (name "/SCK") (class "Default")
      (node (ref "J1") (pin "7") (pinfunction "7_7") (pintype "passive"))
      (node (ref "U1") (pin "17") (pinfunction "PB5_(SCK/PCINT5)_17") (pintype "bidirectional"))
    )
    (net (code "18") (name "/SCL") (class "Default")
      (node (ref "P3") (pin "2") (pinfunction "2_2") (pintype "passive"))
      (node (ref "U1") (pin "28") (pinfunction "PC5_(ADC5/SCL/PCINT13)_28") (pintype "bidirectional"))
    )
    (net (code "19") (name "/SDA") (class "Default")
      (node (ref "P3") (pin "1") (pinfunction "1_1") (pintype "passive"))
      (node (ref "U1") (pin "27") (pinfunction "PC4_(ADC4/SDA/PCINT12)_27") (pintype "bidirectional"))
    )
    (net (code "20") (name "/SPEAKER_IN") (class "Default")
      (node (ref "LS1") (pin "1") (pinfunction "+_1") (pintype "passive"))
      (node (ref "U1") (pin "12") (pinfunction "PB0_(PCINT0/CLKO/ICP1)_12") (pintype "bidirectional"))
    )
    (net (code "21") (name "/STARTER_EN") (class "Default")
      (node (ref "R24") (pin "1") (pinfunction "1_1") (pintype "passive"))
      (node (ref "U1") (pin "11") (pinfunction "PD7_(PCINT23/AIN1)_11") (pintype "bidirectional"))
    )
    (net (code "22") (name "/TX") (class "Default")
      (node (ref "P1") (pin "2") (pinfunction "2_2") (pintype "passive"))
      (node (ref "U1") (pin "31") (pinfunction "PD1_(TXD/PCINT17)_31") (pintype "bidirectional"))
    )
    (net (code "23") (name "/UI_BUTTON_1") (class "Default")
      (node (ref "P2") (pin "2") (pinfunction "2_2") (pintype "passive"))
      (node (ref "R2") (pin "1") (pinfunction "1_1") (pintype "passive"))
      (node (ref "U1") (pin "13") (pinfunction "PB1_(PCINT1/OC1A)_13") (pintype "bidirectional"))
    )
    (net (code "24") (name "/UI_BUTTON_2") (class "Default")
      (node (ref "P9") (pin "2") (pinfunction "2_2") (pintype "passive"))
      (node (ref "R36") (pin "1") (pinfunction "1_1") (pintype "passive"))
      (node (ref "U1") (pin "14") (pinfunction "PB2_(PCINT2/~{SS}/OC1B)_14") (pintype "bidirectional"))
    )
    (net (code "25") (name "/VIN") (class "Default")
      (node (ref "C20") (pin "2") (pinfunction "2_2") (pintype "passive"))
      (node (ref "C24") (pin "1") (pinfunction "1_1") (pintype "passive"))
      (node (ref "C25") (pin "1") (pinfunction "1_1") (pintype "passive"))
      (node (ref "C26") (pin "1") (pinfunction "1_1") (pintype "passive"))
      (node (ref "C27") (pin "1") (pinfunction "1_1") (pintype "passive"))
      (node (ref "C28") (pin "1") (pinfunction "1_1") (pintype "passive"))
      (node (ref "C29") (pin "1") (pinfunction "1_1") (pintype "passive"))
      (node (ref "C30") (pin "1") (pinfunction "1_1") (pintype "passive"))
      (node (ref "C31") (pin "1") (pinfunction "1_1") (pintype "passive"))
      (node (ref "IC2") (pin "20") (pinfunction "VIN_20") (pintype "passive"))
      (node (ref "Q2") (pin "5-6-7-8") (pinfunction "D_5-6-7-8") (pintype "passive"))
      (node (ref "Q3") (pin "5-6-7-8") (pinfunction "D_5-6-7-8") (pintype "passive"))
      (node (ref "U4") (pin "5") (pinfunction "D_5") (pintype "passive"))
      (node (ref "U4") (pin "6") (pinfunction "D_6") (pintype "passive"))
      (node (ref "U4") (pin "7") (pinfunction "D_7") (pintype "passive"))
      (node (ref "U4") (pin "8") (pinfunction "D_8") (pintype "passive"))
    )
    (net (code "26") (name "/VOUT") (class "Default")
      (node (ref "C11") (pin "1") (pinfunction "1_1") (pintype "passive"))
      (node (ref "C38") (pin "1") (pinfunction "1_1") (pintype "passive"))
      (node (ref "C43") (pin "1") (pinfunction "1_1") (pintype "passive"))
      (node (ref "C44") (pin "1") (pinfunction "1_1") (pintype "passive"))
      (node (ref "C45") (pin "1") (pinfunction "1_1") (pintype "passive"))
      (node (ref "C9") (pin "1") (pinfunction "1_1") (pintype "passive"))
      (node (ref "IC2") (pin "3") (pinfunction "EXTVCC_3") (pintype "passive"))
      (node (ref "IC2") (pin "5") (pinfunction "CSN_5") (pintype "passive"))
      (node (ref "R13") (pin "2") (pinfunction "2_2") (pintype "passive"))
      (node (ref "R18") (pin "1") (pinfunction "1_1") (pintype "passive"))
      (node (ref "R26") (pin "2") (pinfunction "2_2") (pintype "passive"))
      (node (ref "R5") (pin "2") (pinfunction "2_2") (pintype "passive"))
      (node (ref "U2") (pin "5") (pinfunction "D_5") (pintype "passive"))
      (node (ref "U3") (pin "5") (pinfunction "D_5") (pintype "passive"))
    )
    (net (code "27") (name "/VREF") (class "Default")
      (node (ref "C10") (pin "1") (pinfunction "1_1") (pintype "passive"))
      (node (ref "IC2") (pin "11") (pinfunction "TMR_11") (pintype "passive"))
      (node (ref "IC2") (pin "14") (pinfunction "VREF_14") (pintype "passive"))
      (node (ref "P8") (pin "3") (pinfunction "3_3") (pintype "passive"))
    )
    (net (code "28") (name "GND") (class "Default")
      (node (ref "C1") (pin "2") (pinfunction "2_2") (pintype "passive"))
      (node (ref "C10") (pin "2") (pinfunction "2_2") (pintype "passive"))
      (node (ref "C11") (pin "2") (pinfunction "2_2") (pintype "passive"))
      (node (ref "C12") (pin "2") (pinfunction "2_2") (pintype "passive"))
      (node (ref "C13") (pin "2") (pinfunction "2_2") (pintype "passive"))
      (node (ref "C14") (pin "2") (pinfunction "2_2") (pintype "passive"))
      (node (ref "C15") (pin "1") (pinfunction "1_1") (pintype "passive"))
      (node (ref "C16") (pin "2") (pinfunction "2_2") (pintype "passive"))
      (node (ref "C17") (pin "2") (pinfunction "-_2") (pintype "passive"))
      (node (ref "C19") (pin "1") (pinfunction "1_1") (pintype "passive"))
      (node (ref "C2") (pin "2") (pinfunction "2_2") (pintype "passive"))
      (node (ref "C20") (pin "1") (pinfunction "1_1") (pintype "passive"))
      (node (ref "C22") (pin "2") (pinfunction "2_2") (pintype "passive"))
      (node (ref "C23") (pin "2") (pinfunction "2_2") (pintype "passive"))
      (node (ref "C24") (pin "2") (pinfunction "2_2") (pintype "passive"))
      (node (ref "C25") (pin "2") (pinfunction "2_2") (pintype "passive"))
      (node (ref "C26") (pin "2") (pinfunction "2_2") (pintype "passive"))
      (node (ref "C27") (pin "2") (pinfunction "2_2") (pintype "passive"))
      (node (ref "C28") (pin "2") (pinfunction "2_2") (pintype "passive"))
      (node (ref "C29") (pin "2") (pinfunction "2_2") (pintype "passive"))
      (node (ref "C3") (pin "1") (pinfunction "1_1") (pintype "passive"))
      (node (ref "C30") (pin "2") (pinfunction "2_2") (pintype "passive"))
      (node (ref "C31") (pin "2") (pinfunction "2_2") (pintype "passive"))
      (node (ref "C4") (pin "1") (pinfunction "1_1") (pintype "passive"))
      (node (ref "C42") (pin "2") (pinfunction "2_2") (pintype "passive"))
      (node (ref "C43") (pin "2") (pinfunction "2_2") (pintype "passive"))
      (node (ref "C44") (pin "2") (pinfunction "2_2") (pintype "passive"))
      (node (ref "C45") (pin "2") (pinfunction "2_2") (pintype "passive"))
      (node (ref "C47") (pin "2") (pinfunction "2_2") (pintype "passive"))
      (node (ref "C48") (pin "2") (pinfunction "-_2") (pintype "passive"))
      (node (ref "C5") (pin "2") (pinfunction "2_2") (pintype "passive"))
      (node (ref "C6") (pin "2") (pinfunction "-_2") (pintype "passive"))
      (node (ref "C7") (pin "2") (pinfunction "2_2") (pintype "passive"))
      (node (ref "IC1") (pin "3") (pinfunction "FIN_(NC)_3") (pintype "passive"))
      (node (ref "IC2") (pin "1") (pinfunction "PGND_1") (pintype "passive"))
      (node (ref "IC2") (pin "16") (pinfunction "IC1_16") (pintype "passive"))
      (node (ref "IC2") (pin "25") (pinfunction "SGND/EP_25") (pintype "passive"))
      (node (ref "IC3") (pin "2") (pinfunction "GND_2") (pintype "passive"))
      (node (ref "IC3") (pin "7") (pinfunction "OV_7") (pintype "passive"))
      (node (ref "J1") (pin "10") (pinfunction "10_10") (pintype "passive"))
      (node (ref "J1") (pin "4") (pinfunction "4_4") (pintype "passive"))
      (node (ref "J1") (pin "6") (pinfunction "6_6") (pintype "passive"))
      (node (ref "J1") (pin "8") (pinfunction "8_8") (pintype "passive"))
      (node (ref "LS1") (pin "2") (pinfunction "-_2") (pintype "passive"))
      (node (ref "P1") (pin "6") (pinfunction "6_6") (pintype "passive"))
      (node (ref "P3") (pin "4") (pinfunction "4_4") (pintype "passive"))
      (node (ref "Q4") (pin "1") (pinfunction "S_1") (pintype "passive"))
      (node (ref "Q4") (pin "2") (pinfunction "S_2") (pintype "passive"))
      (node (ref "Q4") (pin "3") (pinfunction "S_3") (pintype "passive"))
      (node (ref "Q5") (pin "1") (pinfunction "S_1") (pintype "passive"))
      (node (ref "Q5") (pin "2") (pinfunction "S_2") (pintype "passive"))
      (node (ref "Q5") (pin "3") (pinfunction "S_3") (pintype "passive"))
      (node (ref "Q6") (pin "4") (pinfunction "S_4") (pintype "passive"))
      (node (ref "Q7") (pin "4") (pinfunction "S_4") (pintype "passive"))
      (node (ref "R12") (pin "1") (pinfunction "1_1") (pintype "passive"))
      (node (ref "R2") (pin "2") (pinfunction "2_2") (pintype "passive"))
      (node (ref "R20") (pin "2") (pinfunction "2_2") (pintype "passive"))
      (node (ref "R23") (pin "2") (pinfunction "2_2") (pintype "passive"))
      (node (ref "R25") (pin "2") (pinfunction "2_2") (pintype "passive"))
      (node (ref "R36") (pin "2") (pinfunction "2_2") (pintype "passive"))
      (node (ref "R4") (pin "2") (pinfunction "2_2") (pintype "passive"))
      (node (ref "R6") (pin "2") (pinfunction "2_2") (pintype "passive"))
      (node (ref "R8") (pin "2") (pinfunction "2_2") (pintype "passive"))
      (node (ref "SW1") (pin "3") (pinfunction "3_3") (pintype "passive"))
      (node (ref "SW1") (pin "4") (pinfunction "4_4") (pintype "passive"))
      (node (ref "U1") (pin "21") (pinfunction "GND_21") (pintype "power_in"))
      (node (ref "U1") (pin "3") (pinfunction "GND_3") (pintype "power_in"))
      (node (ref "U1") (pin "5") (pinfunction "GND_5") (pintype "power_in"))
    )
    (net (code "29") (name "Net-(C8-Pad2)") (class "Default")
      (node (ref "C8") (pin "2") (pinfunction "2_2") (pintype "passive"))
      (node (ref "P1") (pin "1") (pinfunction "1_1") (pintype "passive"))
    )
    (net (code "30") (name "Net-(C14-Pad1)") (class "Default")
      (node (ref "C14") (pin "1") (pinfunction "1_1") (pintype "passive"))
      (node (ref "R9") (pin "2") (pinfunction "2_2") (pintype "passive"))
    )
    (net (code "31") (name "Net-(C23-Pad1)") (class "Default")
      (node (ref "C23") (pin "1") (pinfunction "1_1") (pintype "passive"))
      (node (ref "R21") (pin "2") (pinfunction "2_2") (pintype "passive"))
      (node (ref "R22") (pin "1") (pinfunction "1_1") (pintype "passive"))
    )
    (net (code "32") (name "Net-(C38-Pad2)") (class "Default")
      (node (ref "C38") (pin "2") (pinfunction "2_2") (pintype "passive"))
      (node (ref "C39") (pin "1") (pinfunction "1_1") (pintype "passive"))
    )
    (net (code "33") (name "Net-(C39-Pad2)") (class "Default")
      (node (ref "C39") (pin "2") (pinfunction "2_2") (pintype "passive"))
      (node (ref "C40") (pin "1") (pinfunction "1_1") (pintype "passive"))
    )
    (net (code "34") (name "Net-(C40-Pad2)") (class "Default")
      (node (ref "C40") (pin "2") (pinfunction "2_2") (pintype "passive"))
      (node (ref "C41") (pin "1") (pinfunction "1_1") (pintype "passive"))
    )
    (net (code "35") (name "Net-(C41-Pad2)") (class "Default")
      (node (ref "C41") (pin "2") (pinfunction "2_2") (pintype "passive"))
      (node (ref "C42") (pin "1") (pinfunction "1_1") (pintype "passive"))
    )
    (net (code "36") (name "Net-(D1-A)") (class "Default")
      (node (ref "D1") (pin "2") (pinfunction "A_2") (pintype "passive"))
      (node (ref "Q7") (pin "1") (pinfunction "D_1_1") (pintype "passive"))
      (node (ref "Q7") (pin "2") (pinfunction "D_2_2") (pintype "passive"))
      (node (ref "Q7") (pin "5") (pinfunction "D_3_5") (pintype "passive"))
      (node (ref "Q7") (pin "6") (pinfunction "D_4_6") (pintype "passive"))
      (node (ref "RE") (pin "1") (pinfunction "COIL_2_1") (pintype "passive"))
    )
    (net (code "37") (name "Net-(D2-K)") (class "Default")
      (node (ref "C21") (pin "1") (pinfunction "1_1") (pintype "passive"))
      (node (ref "D2") (pin "1") (pinfunction "K_1") (pintype "passive"))
      (node (ref "IC2") (pin "23") (pinfunction "BST_23") (pintype "passive"))
    )
    (net (code "38") (name "Net-(IC2-COMP)") (class "Default")
      (node (ref "C13") (pin "1") (pinfunction "1_1") (pintype "passive"))
      (node (ref "IC2") (pin "10") (pinfunction "COMP_10") (pintype "passive"))
      (node (ref "R9") (pin "1") (pinfunction "1_1") (pintype "passive"))
    )
    (net (code "39") (name "Net-(IC2-CSP)") (class "Default")
      (node (ref "C9") (pin "2") (pinfunction "2_2") (pintype "passive"))
      (node (ref "IC2") (pin "4") (pinfunction "CSP_4") (pintype "passive"))
      (node (ref "R27") (pin "2") (pinfunction "2_2") (pintype "passive"))
    )
    (net (code "40") (name "Net-(IC2-DH)") (class "Default")
      (node (ref "IC2") (pin "21") (pinfunction "DH_21") (pintype "passive"))
      (node (ref "R16") (pin "1") (pinfunction "1_1") (pintype "passive"))
      (node (ref "R17") (pin "2") (pinfunction "2_2") (pintype "passive"))
    )
    (net (code "41") (name "Net-(IC2-DL)") (class "Default")
      (node (ref "IC2") (pin "24") (pinfunction "DL_24") (pintype "passive"))
      (node (ref "R14") (pin "2") (pinfunction "2_2") (pintype "passive"))
      (node (ref "R15") (pin "1") (pinfunction "1_1") (pintype "passive"))
    )
    (net (code "42") (name "Net-(IC2-EN{slash}UVLO)") (class "Default")
      (node (ref "IC2") (pin "17") (pinfunction "EN/UVLO_17") (pintype "passive"))
      (node (ref "Q6") (pin "1") (pinfunction "D_1_1") (pintype "passive"))
      (node (ref "Q6") (pin "2") (pinfunction "D_2_2") (pintype "passive"))
      (node (ref "Q6") (pin "5") (pinfunction "D_3_5") (pintype "passive"))
      (node (ref "Q6") (pin "6") (pinfunction "D_4_6") (pintype "passive"))
      (node (ref "R7") (pin "2") (pinfunction "2_2") (pintype "passive"))
      (node (ref "R8") (pin "1") (pinfunction "1_1") (pintype "passive"))
    )
    (net (code "43") (name "Net-(IC2-FB)") (class "Default")
      (node (ref "C16") (pin "1") (pinfunction "1_1") (pintype "passive"))
      (node (ref "IC2") (pin "9") (pinfunction "FB_9") (pintype "passive"))
      (node (ref "R12") (pin "2") (pinfunction "2_2") (pintype "passive"))
      (node (ref "R13") (pin "1") (pinfunction "1_1") (pintype "passive"))
    )
    (net (code "44") (name "Net-(IC2-GATEN)") (class "Default")
      (node (ref "C18") (pin "1") (pinfunction "1_1") (pintype "passive"))
      (node (ref "IC2") (pin "19") (pinfunction "GATEN_19") (pintype "passive"))
      (node (ref "U4") (pin "4") (pinfunction "G_4") (pintype "passive"))
    )
    (net (code "45") (name "Net-(IC2-ILIM)") (class "Default")
      (node (ref "IC2") (pin "13") (pinfunction "ILIM_13") (pintype "passive"))
      (node (ref "P8") (pin "2") (pinfunction "2_2") (pintype "passive"))
    )
    (net (code "46") (name "Net-(IC2-LX)") (class "Default")
      (node (ref "C21") (pin "2") (pinfunction "2_2") (pintype "passive"))
      (node (ref "IC2") (pin "22") (pinfunction "LX_22") (pintype "passive"))
      (node (ref "L1") (pin "1") (pinfunction "1_1") (pintype "passive"))
      (node (ref "Q2") (pin "1") (pinfunction "S_1") (pintype "passive"))
      (node (ref "Q2") (pin "2") (pinfunction "S_2") (pintype "passive"))
      (node (ref "Q2") (pin "3") (pinfunction "S_3") (pintype "passive"))
      (node (ref "Q3") (pin "1") (pinfunction "S_1") (pintype "passive"))
      (node (ref "Q3") (pin "2") (pinfunction "S_2") (pintype "passive"))
      (node (ref "Q3") (pin "3") (pinfunction "S_3") (pintype "passive"))
      (node (ref "Q4") (pin "5-6-7-8") (pinfunction "D_5-6-7-8") (pintype "passive"))
      (node (ref "Q5") (pin "5-6-7-8") (pinfunction "D_5-6-7-8") (pintype "passive"))
    )
    (net (code "47") (name "Net-(IC2-OVI)") (class "Default")
      (node (ref "IC2") (pin "15") (pinfunction "OVI_15") (pintype "passive"))
      (node (ref "R5") (pin "1") (pinfunction "1_1") (pintype "passive"))
      (node (ref "R6") (pin "1") (pinfunction "1_1") (pintype "passive"))
    )
    (net (code "48") (name "Net-(IC3-VCAP)") (class "Default")
      (node (ref "C46") (pin "2") (pinfunction "2_2") (pintype "passive"))
      (node (ref "IC3") (pin "4") (pinfunction "VCAP_4") (pintype "passive"))
    )
    (net (code "49") (name "Net-(Q2-G)") (class "Default")
      (node (ref "Q2") (pin "4") (pinfunction "G_4") (pintype "passive"))
      (node (ref "R16") (pin "2") (pinfunction "2_2") (pintype "passive"))
    )
    (net (code "50") (name "Net-(Q3-G)") (class "Default")
      (node (ref "Q3") (pin "4") (pinfunction "G_4") (pintype "passive"))
      (node (ref "R17") (pin "1") (pinfunction "1_1") (pintype "passive"))
    )
    (net (code "51") (name "Net-(Q4-G)") (class "Default")
      (node (ref "Q4") (pin "4") (pinfunction "G_4") (pintype "passive"))
      (node (ref "R14") (pin "1") (pinfunction "1_1") (pintype "passive"))
    )
    (net (code "52") (name "Net-(Q5-G)") (class "Default")
      (node (ref "Q5") (pin "4") (pinfunction "G_4") (pintype "passive"))
      (node (ref "R15") (pin "2") (pinfunction "2_2") (pintype "passive"))
    )
    (net (code "53") (name "Net-(Q6-G)") (class "Default")
      (node (ref "Q6") (pin "3") (pinfunction "G_3") (pintype "passive"))
      (node (ref "R3") (pin "2") (pinfunction "2_2") (pintype "passive"))
      (node (ref "R4") (pin "1") (pinfunction "1_1") (pintype "passive"))
    )
    (net (code "54") (name "Net-(Q7-G)") (class "Default")
      (node (ref "Q7") (pin "3") (pinfunction "G_3") (pintype "passive"))
      (node (ref "R24") (pin "2") (pinfunction "2_2") (pintype "passive"))
      (node (ref "R25") (pin "1") (pinfunction "1_1") (pintype "passive"))
    )
    (net (code "55") (name "Net-(R19-Pad2)") (class "Default")
      (node (ref "R19") (pin "2") (pinfunction "2_2") (pintype "passive"))
      (node (ref "R20") (pin "1") (pinfunction "1_1") (pintype "passive"))
    )
    (net (code "56") (name "Net-(R22-Pad2)") (class "Default")
      (node (ref "R22") (pin "2") (pinfunction "2_2") (pintype "passive"))
      (node (ref "R23") (pin "1") (pinfunction "1_1") (pintype "passive"))
    )
    (net (code "57") (name "Net-(U1-AREF)") (class "Default")
      (node (ref "C2") (pin "1") (pinfunction "1_1") (pintype "passive"))
      (node (ref "U1") (pin "20") (pinfunction "AREF_20") (pintype "passive"))
    )
    (net (code "58") (name "Net-(U1-PB6_(PCINT6{slash}XTAL1{slash}TOSC1))") (class "Default")
      (node (ref "C3") (pin "2") (pinfunction "2_2") (pintype "passive"))
      (node (ref "U1") (pin "7") (pinfunction "PB6_(PCINT6/XTAL1/TOSC1)_7") (pintype "bidirectional"))
      (node (ref "Y1") (pin "2") (pinfunction "X2_2") (pintype "passive"))
    )
    (net (code "59") (name "Net-(U1-PB7_(PCINT7{slash}XTAL2{slash}TOSC2))") (class "Default")
      (node (ref "C4") (pin "2") (pinfunction "2_2") (pintype "passive"))
      (node (ref "U1") (pin "8") (pinfunction "PB7_(PCINT7/XTAL2/TOSC2)_8") (pintype "bidirectional"))
      (node (ref "Y1") (pin "1") (pinfunction "X1_1") (pintype "passive"))
    )
    (net (code "60") (name "VCC") (class "Default")
      (node (ref "C12") (pin "1") (pinfunction "1_1") (pintype "passive"))
      (node (ref "D2") (pin "2") (pinfunction "A_2") (pintype "passive"))
      (node (ref "IC2") (pin "2") (pinfunction "VCC_2") (pintype "passive"))
      (node (ref "R10") (pin "1") (pinfunction "1_1") (pintype "passive"))
      (node (ref "R11") (pin "1") (pinfunction "1_1") (pintype "passive"))
    )
    (net (code "61") (name "unconnected-(IC2-RT{slash}SYNC-Pad12)") (class "Default")
      (node (ref "IC2") (pin "12") (pinfunction "RT/SYNC_12") (pintype "passive"))
    )
    (net (code "62") (name "unconnected-(IC3-N.C-Pad3)") (class "Default")
      (node (ref "IC3") (pin "3") (pinfunction "N.C_3") (pintype "passive"))
    )
    (net (code "63") (name "unconnected-(J1-Pad3)") (class "Default")
      (node (ref "J1") (pin "3") (pinfunction "3_3") (pintype "passive"))
    )
    (net (code "64") (name "unconnected-(P1-Pad5)") (class "Default")
      (node (ref "P1") (pin "5") (pinfunction "5_5") (pintype "passive"))
    )
    (net (code "65") (name "unconnected-(P8-Pad1)") (class "Default")
      (node (ref "P8") (pin "1") (pinfunction "1_1") (pintype "passive"))
    )
    (net (code "66") (name "unconnected-(U1-PC1_(ADC1{slash}PCINT9)-Pad24)") (class "Default")
      (node (ref "U1") (pin "24") (pinfunction "PC1_(ADC1/PCINT9)_24") (pintype "bidirectional"))
    )
    (net (code "67") (name "unconnected-(U1-PC2_(ADC2{slash}PCINT10)-Pad25)") (class "Default")
      (node (ref "U1") (pin "25") (pinfunction "PC2_(ADC2/PCINT10)_25") (pintype "bidirectional"))
    )
    (net (code "68") (name "unconnected-(U1-PC3_(ADC3{slash}PCINT11)-Pad26)") (class "Default")
      (node (ref "U1") (pin "26") (pinfunction "PC3_(ADC3/PCINT11)_26") (pintype "bidirectional"))
    )
    (net (code "69") (name "unconnected-(U1-PD2_(INT0{slash}PCINT18)-Pad32)") (class "Default")
      (node (ref "U1") (pin "32") (pinfunction "PD2_(INT0/PCINT18)_32") (pintype "bidirectional"))
    )
  )
)
